# Grove_-_96x96_OLED_Display_v2_1.net
KiCad netlist of a schematic drawn in EAGLE
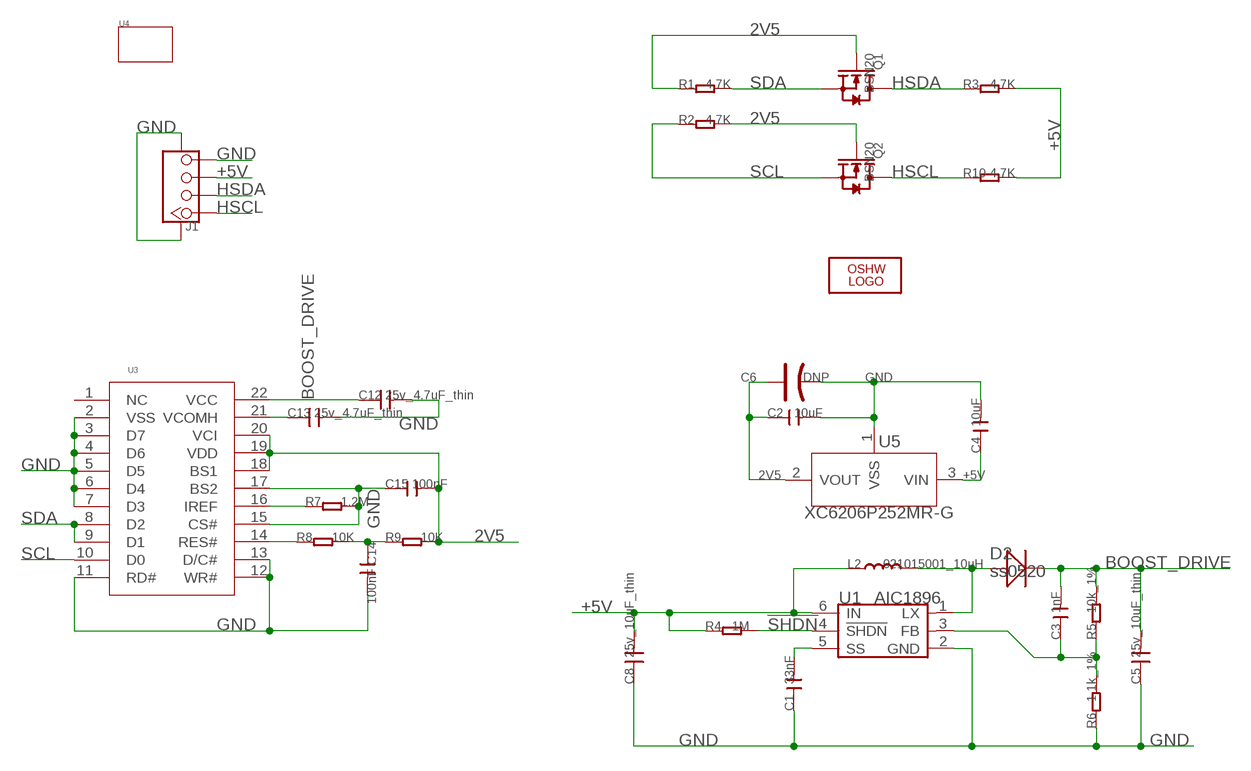
[diagram p0: schematic, sheet 1]

(export (version "E")
  (design (tool "Eeschema 10.0.6"))
  (components
    (comp (ref "C1")
      (value "33nF")
      (footprint "eagle-import:C0603")
      (libsource (lib "eagle-import") (part "C-0603"))
    )
    (comp (ref "C2")
      (value "10uF")
      (footprint "eagle-import:C0805")
      (libsource (lib "eagle-import") (part "C-0805"))
    )
    (comp (ref "C3")
      (value "1nF")
      (footprint "eagle-import:C0603")
      (libsource (lib "eagle-import") (part "C-0603"))
    )
    (comp (ref "C4")
      (value "10uF")
      (footprint "eagle-import:C0805")
      (libsource (lib "eagle-import") (part "C-0805"))
    )
    (comp (ref "C5")
      (value "25v_10uF_thin")
      (footprint "eagle-import:0805")
      (libsource (lib "eagle-import") (part "006-C0805"))
    )
    (comp (ref "C6")
      (value "DNP")
      (footprint "eagle-import:AVX-A")
      (libsource (lib "eagle-import") (part "CAP-AVX-A"))
    )
    (comp (ref "C8")
      (value "25v_10uF_thin")
      (footprint "eagle-import:0805")
      (libsource (lib "eagle-import") (part "006-C0805"))
    )
    (comp (ref "C12")
      (value "25v_4.7uF_thin")
      (footprint "eagle-import:0805")
      (libsource (lib "eagle-import") (part "006-C0805"))
    )
    (comp (ref "C13")
      (value "25v_4.7uF_thin")
      (footprint "eagle-import:0805")
      (libsource (lib "eagle-import") (part "006-C0805"))
    )
    (comp (ref "C14")
      (value "100nF")
      (footprint "eagle-import:C0603")
      (libsource (lib "eagle-import") (part "C-0603"))
    )
    (comp (ref "C15")
      (value "100nF")
      (footprint "eagle-import:C0603")
      (libsource (lib "eagle-import") (part "C-0603"))
    )
    (comp (ref "D2")
      (value "ss0520")
      (footprint "eagle-import:SOD123")
      (libsource (lib "eagle-import") (part "010-DSOD123"))
    )
    (comp (ref "J1")
      (value "TWIG-4P-2.0-SMD-FEMALE-REINFORCE'90D'")
      (footprint "eagle-import:4P-SMD-2.0-90D")
      (libsource (lib "eagle-import") (part "TWIG-4P-2.0-SMD-FEMALE-REINFORCE'90D'"))
    )
    (comp (ref "L2")
      (value "021015001_10uH")
      (footprint "eagle-import:0806")
      (libsource (lib "eagle-import") (part "013-L0806"))
    )
    (comp (ref "LOGO2")
      (value "LOGO-OSHW-FILLX0200-NT")
      (footprint "eagle-import:OSHW_FILLX200_NOTEXT")
      (fields (field (name "PARTNO") "DNP"))
      (libsource (lib "eagle-import") (part "LOGO-OSHW-FILLX0200-NT"))
    )
    (comp (ref "Q1")
      (value "BSN20")
      (footprint "eagle-import:SOT23")
      (libsource (lib "eagle-import") (part "MOSFET-N'SOT23'"))
    )
    (comp (ref "Q2")
      (value "BSN20")
      (footprint "eagle-import:SOT23")
      (libsource (lib "eagle-import") (part "MOSFET-N'SOT23'"))
    )
    (comp (ref "R1")
      (value "4.7K")
      (footprint "eagle-import:R0603")
      (libsource (lib "eagle-import") (part "R-0603"))
    )
    (comp (ref "R2")
      (value "4.7K")
      (footprint "eagle-import:R0603")
      (libsource (lib "eagle-import") (part "R-0603"))
    )
    (comp (ref "R3")
      (value "4.7K")
      (footprint "eagle-import:R0603")
      (libsource (lib "eagle-import") (part "R-0603"))
    )
    (comp (ref "R4")
      (value "1M")
      (footprint "eagle-import:R0603")
      (libsource (lib "eagle-import") (part "R-0603"))
    )
    (comp (ref "R5")
      (value "10k_1%")
      (footprint "eagle-import:R0603")
      (libsource (lib "eagle-import") (part "R-0603"))
    )
    (comp (ref "R6")
      (value "1.1k_1%")
      (footprint "eagle-import:R0603")
      (libsource (lib "eagle-import") (part "R-0603"))
    )
    (comp (ref "R7")
      (value "1.2M")
      (footprint "eagle-import:0603")
      (libsource (lib "eagle-import") (part "005-R0603"))
    )
    (comp (ref "R8")
      (value "10K")
      (footprint "eagle-import:0603")
      (libsource (lib "eagle-import") (part "005-R0603"))
    )
    (comp (ref "R9")
      (value "10K")
      (footprint "eagle-import:0603")
      (libsource (lib "eagle-import") (part "005-R0603"))
    )
    (comp (ref "R10")
      (value "4.7K")
      (footprint "eagle-import:R0603")
      (libsource (lib "eagle-import") (part "R-0603"))
    )
    (comp (ref "U1")
      (value "AIC1896")
      (footprint "eagle-import:SOT23-6")
      (libsource (lib "eagle-import") (part "AIC1896"))
    )
    (comp (ref "U3")
      (value "LY120-096096")
      (footprint "eagle-import:LY120-096096")
      (libsource (lib "eagle-import") (part "LY120-096096"))
    )
    (comp (ref "U4")
      (value "TWIG-2X2U")
      (footprint "eagle-import:2X2U-DIM-W_-DRILL")
      (libsource (lib "eagle-import") (part "TWIG-2X2U"))
    )
    (comp (ref "U5")
      (value "XC6206P252MR-G")
      (footprint "eagle-import:SOT23")
      (libsource (lib "eagle-import") (part "XC6206MR"))
    )
  )
  (nets
    (net (code "1") (name "/+5V") (class "Default")
      (node (ref "C4") (pin "1") (pinfunction "1_1") (pintype "passive"))
      (node (ref "C8") (pin "2") (pinfunction "2_2") (pintype "passive"))
      (node (ref "J1") (pin "3") (pinfunction "3_3") (pintype "bidirectional"))
      (node (ref "L2") (pin "1") (pinfunction "1_1") (pintype "passive"))
      (node (ref "R10") (pin "2") (pinfunction "2_2") (pintype "passive"))
      (node (ref "R3") (pin "2") (pinfunction "2_2") (pintype "passive"))
      (node (ref "R4") (pin "1") (pinfunction "1_1") (pintype "passive"))
      (node (ref "U1") (pin "6") (pinfunction "IN_6") (pintype "input"))
      (node (ref "U5") (pin "3") (pinfunction "VIN_3") (pintype "input"))
    )
    (net (code "2") (name "/2V5") (class "Default")
      (node (ref "C15") (pin "2") (pinfunction "2_2") (pintype "passive"))
      (node (ref "C2") (pin "1") (pinfunction "1_1") (pintype "passive"))
      (node (ref "C6") (pin "+") (pinfunction "+_+") (pintype "passive"))
      (node (ref "Q1") (pin "1") (pinfunction "G_1") (pintype "passive"))
      (node (ref "Q2") (pin "1") (pinfunction "G_1") (pintype "passive"))
      (node (ref "R1") (pin "1") (pinfunction "1_1") (pintype "passive"))
      (node (ref "R2") (pin "2") (pinfunction "2_2") (pintype "passive"))
      (node (ref "R9") (pin "2") (pinfunction "2_2") (pintype "passive"))
      (node (ref "U3") (pin "18") (pinfunction "BS1_18") (pintype "bidirectional"))
      (node (ref "U3") (pin "19") (pinfunction "VDD_19") (pintype "bidirectional"))
      (node (ref "U3") (pin "20") (pinfunction "VCI_20") (pintype "bidirectional"))
      (node (ref "U5") (pin "2") (pinfunction "VOUT_2") (pintype "output"))
    )
    (net (code "3") (name "/BOOST_DRIVE") (class "Default")
      (node (ref "C12") (pin "1") (pinfunction "1_1") (pintype "passive"))
      (node (ref "C3") (pin "2") (pinfunction "2_2") (pintype "passive"))
      (node (ref "C5") (pin "2") (pinfunction "2_2") (pintype "passive"))
      (node (ref "D2") (pin "-") (pinfunction "-_-") (pintype "passive"))
      (node (ref "R5") (pin "2") (pinfunction "2_2") (pintype "passive"))
      (node (ref "U3") (pin "22") (pinfunction "VCC_22") (pintype "bidirectional"))
    )
    (net (code "4") (name "/GND") (class "Default")
      (node (ref "C1") (pin "1") (pinfunction "1_1") (pintype "passive"))
      (node (ref "C12") (pin "2") (pinfunction "2_2") (pintype "passive"))
      (node (ref "C13") (pin "2") (pinfunction "2_2") (pintype "passive"))
      (node (ref "C14") (pin "2") (pinfunction "2_2") (pintype "passive"))
      (node (ref "C15") (pin "1") (pinfunction "1_1") (pintype "passive"))
      (node (ref "C2") (pin "2") (pinfunction "2_2") (pintype "passive"))
      (node (ref "C4") (pin "2") (pinfunction "2_2") (pintype "passive"))
      (node (ref "C5") (pin "1") (pinfunction "1_1") (pintype "passive"))
      (node (ref "C6") (pin "-") (pinfunction "-_-") (pintype "passive"))
      (node (ref "C8") (pin "1") (pinfunction "1_1") (pintype "passive"))
      (node (ref "J1") (pin "4") (pinfunction "4_4") (pintype "bidirectional"))
      (node (ref "J1") (pin "SS1") (pinfunction "SS1_SS1") (pintype "bidirectional"))
      (node (ref "J1") (pin "SS2") (pinfunction "SS2_SS2") (pintype "bidirectional"))
      (node (ref "R6") (pin "1") (pinfunction "1_1") (pintype "passive"))
      (node (ref "R7") (pin "2") (pinfunction "2_2") (pintype "passive"))
      (node (ref "U1") (pin "2") (pinfunction "GND_2") (pintype "power_in"))
      (node (ref "U3") (pin "11") (pinfunction "RD#_11") (pintype "bidirectional"))
      (node (ref "U3") (pin "12") (pinfunction "WR#_12") (pintype "bidirectional"))
      (node (ref "U3") (pin "13") (pinfunction "D/C#_13") (pintype "bidirectional"))
      (node (ref "U3") (pin "15") (pinfunction "CS#_15") (pintype "bidirectional"))
      (node (ref "U3") (pin "17") (pinfunction "BS2_17") (pintype "bidirectional"))
      (node (ref "U3") (pin "2") (pinfunction "VSS_2") (pintype "bidirectional"))
      (node (ref "U3") (pin "3") (pinfunction "D7_3") (pintype "bidirectional"))
      (node (ref "U3") (pin "4") (pinfunction "D6_4") (pintype "bidirectional"))
      (node (ref "U3") (pin "5") (pinfunction "D5_5") (pintype "bidirectional"))
      (node (ref "U3") (pin "6") (pinfunction "D4_6") (pintype "bidirectional"))
      (node (ref "U3") (pin "7") (pinfunction "D3_7") (pintype "bidirectional"))
      (node (ref "U5") (pin "1") (pinfunction "VSS_1") (pintype "power_in"))
    )
    (net (code "5") (name "/HSCL") (class "Default")
      (node (ref "J1") (pin "1") (pinfunction "1_1") (pintype "bidirectional"))
      (node (ref "Q2") (pin "3") (pinfunction "D_3") (pintype "passive"))
      (node (ref "R10") (pin "1") (pinfunction "1_1") (pintype "passive"))
    )
    (net (code "6") (name "/HSDA") (class "Default")
      (node (ref "J1") (pin "2") (pinfunction "2_2") (pintype "bidirectional"))
      (node (ref "Q1") (pin "3") (pinfunction "D_3") (pintype "passive"))
      (node (ref "R3") (pin "1") (pinfunction "1_1") (pintype "passive"))
    )
    (net (code "7") (name "/SCL") (class "Default")
      (node (ref "Q2") (pin "2") (pinfunction "S_2") (pintype "passive"))
      (node (ref "R2") (pin "1") (pinfunction "1_1") (pintype "passive"))
      (node (ref "U3") (pin "10") (pinfunction "D0_10") (pintype "bidirectional"))
    )
    (net (code "8") (name "/SDA") (class "Default")
      (node (ref "Q1") (pin "2") (pinfunction "S_2") (pintype "passive"))
      (node (ref "R1") (pin "2") (pinfunction "2_2") (pintype "passive"))
      (node (ref "U3") (pin "8") (pinfunction "D2_8") (pintype "bidirectional"))
      (node (ref "U3") (pin "9") (pinfunction "D1_9") (pintype "bidirectional"))
    )
    (net (code "9") (name "/~{SHDN}") (class "Default")
      (node (ref "R4") (pin "2") (pinfunction "2_2") (pintype "passive"))
      (node (ref "U1") (pin "4") (pinfunction "~{SHDN}_4") (pintype "input"))
    )
    (net (code "10") (name "Net-(C14-Pad1)") (class "Default")
      (node (ref "C14") (pin "1") (pinfunction "1_1") (pintype "passive"))
      (node (ref "R8") (pin "2") (pinfunction "2_2") (pintype "passive"))
      (node (ref "R9") (pin "1") (pinfunction "1_1") (pintype "passive"))
    )
    (net (code "11") (name "Net-(U1-FB)") (class "Default")
      (node (ref "C3") (pin "1") (pinfunction "1_1") (pintype "passive"))
      (node (ref "R5") (pin "1") (pinfunction "1_1") (pintype "passive"))
      (node (ref "R6") (pin "2") (pinfunction "2_2") (pintype "passive"))
      (node (ref "U1") (pin "3") (pinfunction "FB_3") (pintype "input"))
    )
    (net (code "12") (name "Net-(U1-LX)") (class "Default")
      (node (ref "D2") (pin "+") (pinfunction "+_+") (pintype "passive"))
      (node (ref "L2") (pin "2") (pinfunction "2_2") (pintype "passive"))
      (node (ref "U1") (pin "1") (pinfunction "LX_1") (pintype "output"))
    )
    (net (code "13") (name "Net-(U1-SS)") (class "Default")
      (node (ref "C1") (pin "2") (pinfunction "2_2") (pintype "passive"))
      (node (ref "U1") (pin "5") (pinfunction "SS_5") (pintype "input"))
    )
    (net (code "14") (name "Net-(U3-IREF)") (class "Default")
      (node (ref "R7") (pin "1") (pinfunction "1_1") (pintype "passive"))
      (node (ref "U3") (pin "16") (pinfunction "IREF_16") (pintype "bidirectional"))
    )
    (net (code "15") (name "Net-(U3-RES#)") (class "Default")
      (node (ref "R8") (pin "1") (pinfunction "1_1") (pintype "passive"))
      (node (ref "U3") (pin "14") (pinfunction "RES#_14") (pintype "bidirectional"))
    )
    (net (code "16") (name "Net-(U3-VCOMH)") (class "Default")
      (node (ref "C13") (pin "1") (pinfunction "1_1") (pintype "passive"))
      (node (ref "U3") (pin "21") (pinfunction "VCOMH_21") (pintype "bidirectional"))
    )
    (net (code "17") (name "unconnected-(U3-NC-Pad1)") (class "Default")
      (node (ref "U3") (pin "1") (pinfunction "NC_1") (pintype "bidirectional"))
    )
  )
)
